# mainboard.net
KiCad netlist of a schematic drawn in EAGLE
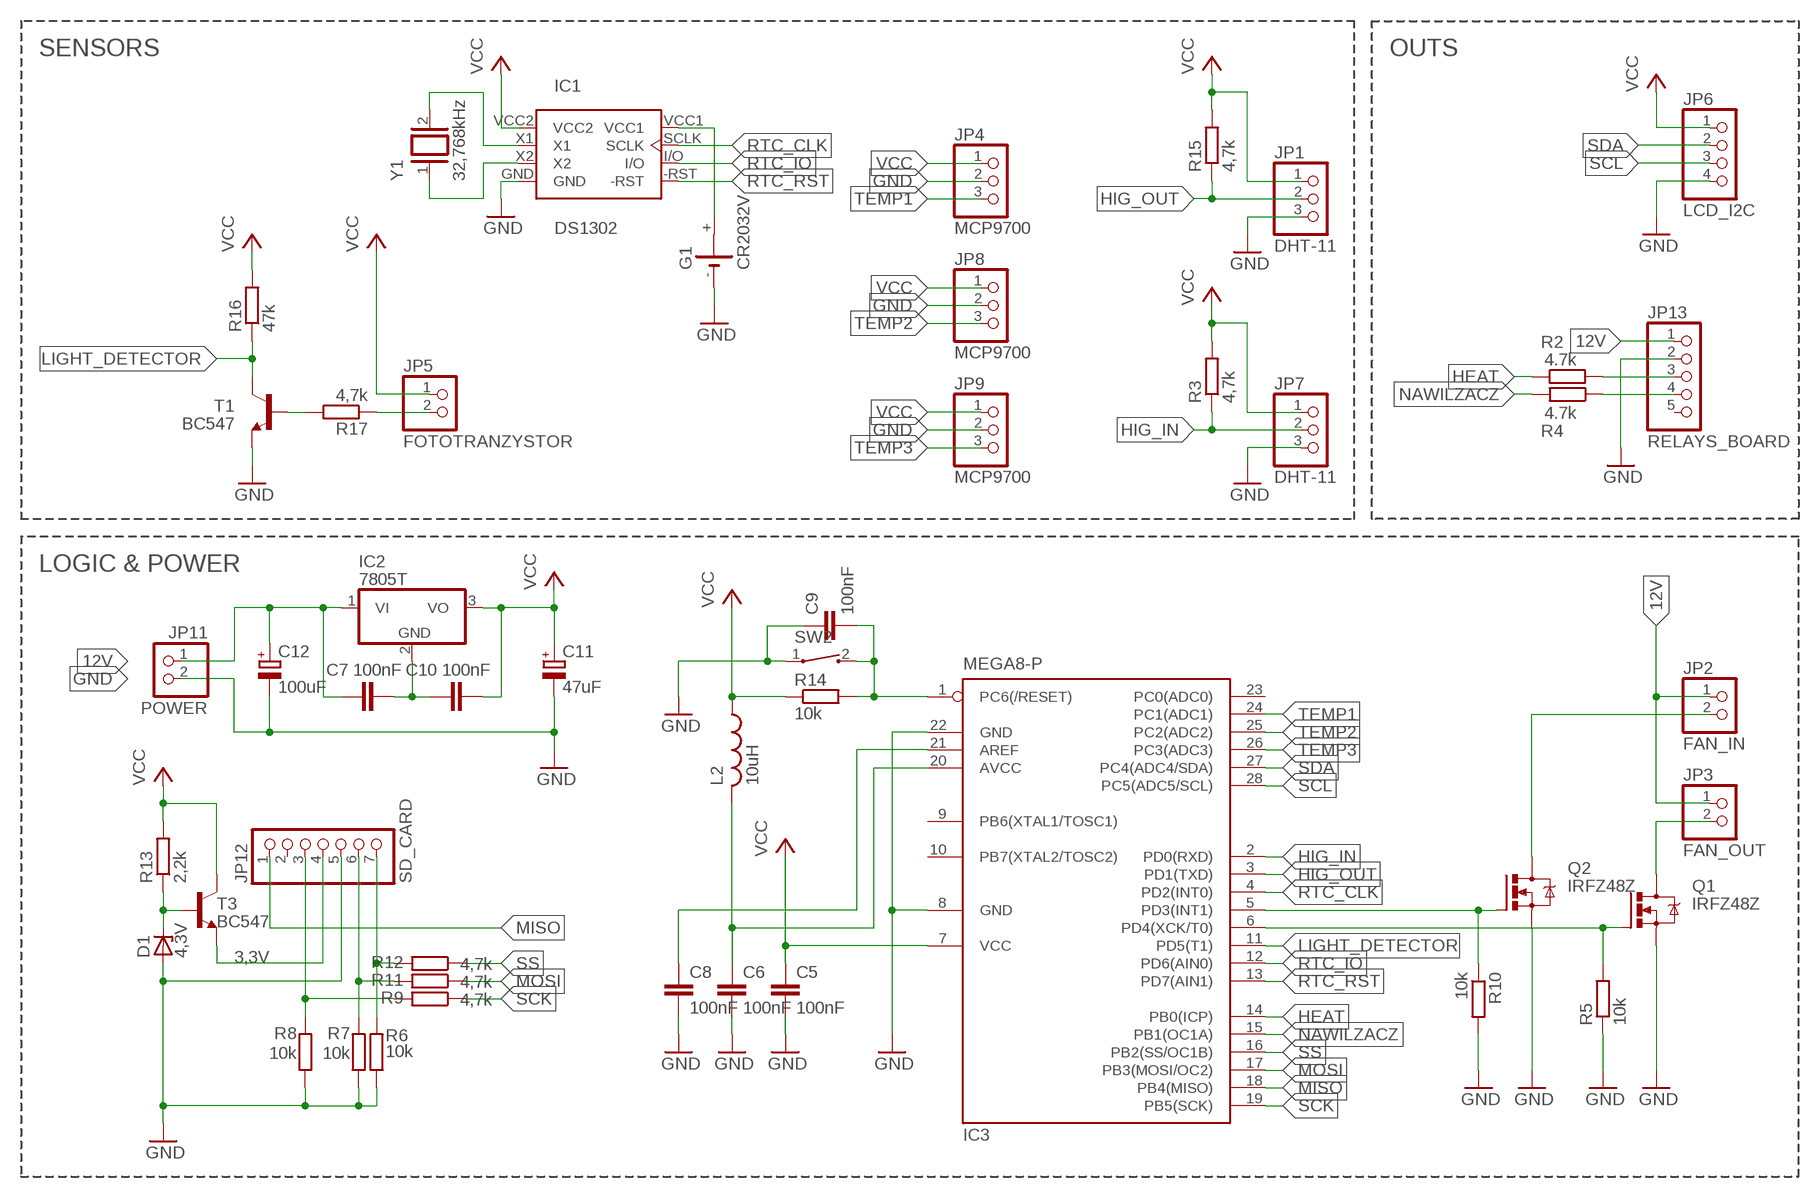
[diagram p0: schematic, sheet 1]

(export (version "E")
  (design (tool "Eeschema 10.0.6"))
  (components
    (comp (ref "C5")
      (value "100nF")
      (footprint "eagle-import:C050-030X075")
      (libsource (lib "eagle-import") (part "C-EU050-030X075"))
    )
    (comp (ref "C6")
      (value "100nF")
      (footprint "eagle-import:C050-030X075")
      (libsource (lib "eagle-import") (part "C-EU050-030X075"))
    )
    (comp (ref "C7")
      (value "100nF")
      (footprint "eagle-import:C050-024X044")
      (libsource (lib "eagle-import") (part "C-EU050-024X044"))
    )
    (comp (ref "C8")
      (value "100nF")
      (footprint "eagle-import:C050-030X075")
      (libsource (lib "eagle-import") (part "C-EU050-030X075"))
    )
    (comp (ref "C9")
      (value "100nF")
      (footprint "eagle-import:C050-030X075")
      (libsource (lib "eagle-import") (part "C-EU050-030X075"))
    )
    (comp (ref "C10")
      (value "100nF")
      (footprint "eagle-import:C050-024X044")
      (libsource (lib "eagle-import") (part "C-EU050-024X044"))
    )
    (comp (ref "C11")
      (value "47uF")
      (footprint "eagle-import:E2,5-6")
      (libsource (lib "eagle-import") (part "CPOL-EUE2.5-6"))
    )
    (comp (ref "C12")
      (value "100uF")
      (footprint "eagle-import:E2,5-6")
      (libsource (lib "eagle-import") (part "CPOL-EUE2.5-6"))
    )
    (comp (ref "D1")
      (value "4,3V")
      (footprint "eagle-import:C1702-15")
      (libsource (lib "eagle-import") (part "ZENER-DIODEC1702-15"))
    )
    (comp (ref "G1")
      (value "CR2032V")
      (footprint "eagle-import:CR2032V")
      (libsource (lib "eagle-import") (part "CR2032V"))
    )
    (comp (ref "IC1")
      (value "DS1302")
      (footprint "eagle-import:DIL08")
      (libsource (lib "eagle-import") (part "DS1302"))
    )
    (comp (ref "IC2")
      (value "7805T")
      (footprint "eagle-import:TO220H")
      (libsource (lib "eagle-import") (part "78T05"))
    )
    (comp (ref "IC3")
      (value "MEGA8-P")
      (footprint "eagle-import:DIL28-3")
      (libsource (lib "eagle-import") (part "MEGA8-P"))
    )
    (comp (ref "JP1")
      (value "DHT-11")
      (footprint "eagle-import:1X03")
      (libsource (lib "eagle-import") (part "PINHD-1X3"))
    )
    (comp (ref "JP2")
      (value "FAN_IN")
      (footprint "eagle-import:1X02")
      (libsource (lib "eagle-import") (part "PINHD-1X2"))
    )
    (comp (ref "JP3")
      (value "FAN_OUT")
      (footprint "eagle-import:1X02")
      (libsource (lib "eagle-import") (part "PINHD-1X2"))
    )
    (comp (ref "JP4")
      (value "MCP9700")
      (footprint "eagle-import:1X03")
      (libsource (lib "eagle-import") (part "PINHD-1X3"))
    )
    (comp (ref "JP5")
      (value "FOTOTRANZYSTOR")
      (footprint "eagle-import:1X02")
      (libsource (lib "eagle-import") (part "PINHD-1X2"))
    )
    (comp (ref "JP6")
      (value "LCD_I2C")
      (footprint "eagle-import:1X04")
      (libsource (lib "eagle-import") (part "PINHD-1X4"))
    )
    (comp (ref "JP7")
      (value "DHT-11")
      (footprint "eagle-import:1X03")
      (libsource (lib "eagle-import") (part "PINHD-1X3"))
    )
    (comp (ref "JP8")
      (value "MCP9700")
      (footprint "eagle-import:1X03")
      (libsource (lib "eagle-import") (part "PINHD-1X3"))
    )
    (comp (ref "JP9")
      (value "MCP9700")
      (footprint "eagle-import:1X03")
      (libsource (lib "eagle-import") (part "PINHD-1X3"))
    )
    (comp (ref "JP11")
      (value "POWER")
      (footprint "eagle-import:1X02")
      (libsource (lib "eagle-import") (part "PINHD-1X2"))
    )
    (comp (ref "JP12")
      (value "SD_CARD")
      (footprint "eagle-import:1X07")
      (libsource (lib "eagle-import") (part "PINHD-1X7"))
    )
    (comp (ref "JP13")
      (value "RELAYS_BOARD")
      (footprint "eagle-import:1X05")
      (libsource (lib "eagle-import") (part "PINHD-1X5"))
    )
    (comp (ref "L2")
      (value "10uH")
      (footprint "eagle-import:0204_7")
      (libsource (lib "eagle-import") (part "L-US0204/7"))
    )
    (comp (ref "Q1")
      (value "IRFZ48Z")
      (footprint "eagle-import:TO220BH")
      (libsource (lib "eagle-import") (part "IRFZ48Z"))
    )
    (comp (ref "Q2")
      (value "IRFZ48Z")
      (footprint "eagle-import:TO220BH")
      (libsource (lib "eagle-import") (part "IRFZ48Z"))
    )
    (comp (ref "R2")
      (value "4.7k")
      (footprint "eagle-import:0207_10")
      (libsource (lib "eagle-import") (part "R-EU_0207/10"))
    )
    (comp (ref "R3")
      (value "4,7k")
      (footprint "eagle-import:0207_10")
      (libsource (lib "eagle-import") (part "R-EU_0207/10"))
    )
    (comp (ref "R4")
      (value "4.7k")
      (footprint "eagle-import:0207_10")
      (libsource (lib "eagle-import") (part "R-EU_0207/10"))
    )
    (comp (ref "R5")
      (value "10k")
      (footprint "eagle-import:0207_10")
      (libsource (lib "eagle-import") (part "R-EU_0207/10"))
    )
    (comp (ref "R6")
      (value "10k")
      (footprint "eagle-import:0207_10")
      (libsource (lib "eagle-import") (part "R-EU_0207/10"))
    )
    (comp (ref "R7")
      (value "10k")
      (footprint "eagle-import:0207_10")
      (libsource (lib "eagle-import") (part "R-EU_0207/10"))
    )
    (comp (ref "R8")
      (value "10k")
      (footprint "eagle-import:0207_10")
      (libsource (lib "eagle-import") (part "R-EU_0207/10"))
    )
    (comp (ref "R9")
      (value "4,7k")
      (footprint "eagle-import:0207_10")
      (libsource (lib "eagle-import") (part "R-EU_0207/10"))
    )
    (comp (ref "R10")
      (value "10k")
      (footprint "eagle-import:0207_10")
      (libsource (lib "eagle-import") (part "R-EU_0207/10"))
    )
    (comp (ref "R11")
      (value "4,7k")
      (footprint "eagle-import:0207_10")
      (libsource (lib "eagle-import") (part "R-EU_0207/10"))
    )
    (comp (ref "R12")
      (value "4,7k")
      (footprint "eagle-import:0207_10")
      (libsource (lib "eagle-import") (part "R-EU_0207/10"))
    )
    (comp (ref "R13")
      (value "2,2k")
      (footprint "eagle-import:0207_10")
      (libsource (lib "eagle-import") (part "R-EU_0207/10"))
    )
    (comp (ref "R14")
      (value "10k")
      (footprint "eagle-import:0204_7")
      (libsource (lib "eagle-import") (part "R-EU_0204/7"))
    )
    (comp (ref "R15")
      (value "4,7k")
      (footprint "eagle-import:0207_10")
      (libsource (lib "eagle-import") (part "R-EU_0207/10"))
    )
    (comp (ref "R16")
      (value "47k")
      (footprint "eagle-import:0207_10")
      (libsource (lib "eagle-import") (part "R-EU_0207/10"))
    )
    (comp (ref "R17")
      (value "4,7k")
      (footprint "eagle-import:0207_10")
      (libsource (lib "eagle-import") (part "R-EU_0207/10"))
    )
    (comp (ref "SW2")
      (value "CT10-XXXX-G4")
      (footprint "eagle-import:CT10-XXXX-G4")
      (libsource (lib "eagle-import") (part "CT10-XXXX-G4"))
    )
    (comp (ref "T1")
      (value "BC547")
      (footprint "eagle-import:TO92")
      (libsource (lib "eagle-import") (part "BC547"))
    )
    (comp (ref "T3")
      (value "BC547")
      (footprint "eagle-import:TO92")
      (libsource (lib "eagle-import") (part "BC547"))
    )
    (comp (ref "Y1")
      (value "32,768kHz")
      (footprint "eagle-import:QS")
      (libsource (lib "eagle-import") (part "XTAL/S"))
    )
  )
  (nets
    (net (code "1") (name "/3,3V") (class "Default")
      (node (ref "JP12") (pin "4") (pinfunction "4_4") (pintype "passive"))
      (node (ref "T3") (pin "1") (pinfunction "E_1") (pintype "passive"))
    )
    (net (code "2") (name "12V") (class "Default")
      (node (ref "C12") (pin "+") (pinfunction "+_+") (pintype "passive"))
      (node (ref "C7") (pin "1") (pinfunction "1_1") (pintype "passive"))
      (node (ref "IC2") (pin "1") (pinfunction "VI_1") (pintype "input"))
      (node (ref "JP11") (pin "1") (pinfunction "1_1") (pintype "passive"))
      (node (ref "JP13") (pin "1") (pinfunction "1_1") (pintype "passive"))
      (node (ref "JP2") (pin "1") (pinfunction "1_1") (pintype "passive"))
      (node (ref "JP3") (pin "1") (pinfunction "1_1") (pintype "passive"))
    )
    (net (code "3") (name "GND") (class "Default")
      (node (ref "C11") (pin "-") (pinfunction "-_-") (pintype "passive"))
      (node (ref "C12") (pin "-") (pinfunction "-_-") (pintype "passive"))
      (node (ref "C5") (pin "2") (pinfunction "2_2") (pintype "passive"))
      (node (ref "C6") (pin "2") (pinfunction "2_2") (pintype "passive"))
      (node (ref "C8") (pin "2") (pinfunction "2_2") (pintype "passive"))
      (node (ref "C9") (pin "1") (pinfunction "1_1") (pintype "passive"))
      (node (ref "D1") (pin "A") (pinfunction "A_A") (pintype "passive"))
      (node (ref "G1") (pin "-") (pinfunction "-_-") (pintype "passive"))
      (node (ref "IC1") (pin "GND") (pinfunction "GND_GND") (pintype "passive"))
      (node (ref "IC3") (pin "22") (pinfunction "GND_22") (pintype "power_in"))
      (node (ref "IC3") (pin "8") (pinfunction "GND_8") (pintype "power_in"))
      (node (ref "JP1") (pin "3") (pinfunction "3_3") (pintype "passive"))
      (node (ref "JP11") (pin "2") (pinfunction "2_2") (pintype "passive"))
      (node (ref "JP12") (pin "5") (pinfunction "5_5") (pintype "passive"))
      (node (ref "JP13") (pin "2") (pinfunction "2_2") (pintype "passive"))
      (node (ref "JP4") (pin "2") (pinfunction "2_2") (pintype "passive"))
      (node (ref "JP6") (pin "4") (pinfunction "4_4") (pintype "passive"))
      (node (ref "JP7") (pin "3") (pinfunction "3_3") (pintype "passive"))
      (node (ref "JP8") (pin "2") (pinfunction "2_2") (pintype "passive"))
      (node (ref "JP9") (pin "2") (pinfunction "2_2") (pintype "passive"))
      (node (ref "Q1") (pin "S") (pinfunction "S_S") (pintype "passive"))
      (node (ref "Q2") (pin "S") (pinfunction "S_S") (pintype "passive"))
      (node (ref "R10") (pin "2") (pinfunction "2_2") (pintype "passive"))
      (node (ref "R5") (pin "1") (pinfunction "1_1") (pintype "passive"))
      (node (ref "R6") (pin "1") (pinfunction "1_1") (pintype "passive"))
      (node (ref "R7") (pin "1") (pinfunction "1_1") (pintype "passive"))
      (node (ref "R8") (pin "1") (pinfunction "1_1") (pintype "passive"))
      (node (ref "SW2") (pin "1") (pinfunction "1_1") (pintype "passive"))
      (node (ref "T1") (pin "1") (pinfunction "E_1") (pintype "passive"))
    )
    (net (code "4") (name "HEAT") (class "Default")
      (node (ref "IC3") (pin "14") (pinfunction "PB0(ICP)_14") (pintype "bidirectional"))
      (node (ref "R2") (pin "1") (pinfunction "1_1") (pintype "passive"))
    )
    (net (code "5") (name "HIG_IN") (class "Default")
      (node (ref "IC3") (pin "2") (pinfunction "PD0(RXD)_2") (pintype "bidirectional"))
      (node (ref "JP7") (pin "2") (pinfunction "2_2") (pintype "passive"))
      (node (ref "R3") (pin "1") (pinfunction "1_1") (pintype "passive"))
    )
    (net (code "6") (name "HIG_OUT") (class "Default")
      (node (ref "IC3") (pin "3") (pinfunction "PD1(TXD)_3") (pintype "bidirectional"))
      (node (ref "JP1") (pin "2") (pinfunction "2_2") (pintype "passive"))
      (node (ref "R15") (pin "1") (pinfunction "1_1") (pintype "passive"))
    )
    (net (code "7") (name "LIGHT_DETECTOR") (class "Default")
      (node (ref "IC3") (pin "11") (pinfunction "PD5(T1)_11") (pintype "bidirectional"))
      (node (ref "IC3") (pin "6") (pinfunction "PD4(XCK/T0)_6") (pintype "bidirectional"))
      (node (ref "Q1") (pin "G") (pinfunction "G_G") (pintype "passive"))
      (node (ref "R16") (pin "1") (pinfunction "1_1") (pintype "passive"))
      (node (ref "R5") (pin "2") (pinfunction "2_2") (pintype "passive"))
      (node (ref "T1") (pin "3") (pinfunction "C_3") (pintype "passive"))
    )
    (net (code "8") (name "MISO") (class "Default")
      (node (ref "IC3") (pin "18") (pinfunction "PB4(MISO)_18") (pintype "bidirectional"))
      (node (ref "JP12") (pin "1") (pinfunction "1_1") (pintype "passive"))
    )
    (net (code "9") (name "MOSI") (class "Default")
      (node (ref "IC3") (pin "17") (pinfunction "PB3(MOSI/OC2)_17") (pintype "bidirectional"))
      (node (ref "R11") (pin "1") (pinfunction "1_1") (pintype "passive"))
    )
    (net (code "10") (name "NAWILZACZ") (class "Default")
      (node (ref "IC3") (pin "15") (pinfunction "PB1(OC1A)_15") (pintype "bidirectional"))
      (node (ref "R4") (pin "2") (pinfunction "2_2") (pintype "passive"))
    )
    (net (code "11") (name "Net-(G1-Pad+)") (class "Default")
      (node (ref "G1") (pin "+") (pinfunction "+_+") (pintype "passive"))
      (node (ref "IC1") (pin "VCC1") (pinfunction "VCC1_VCC1") (pintype "power_in"))
    )
    (net (code "12") (name "Net-(IC1-PadX1)") (class "Default")
      (node (ref "IC1") (pin "X1") (pinfunction "X1_X1") (pintype "tri_state"))
      (node (ref "Y1") (pin "2") (pinfunction "2_2") (pintype "passive"))
    )
    (net (code "13") (name "Net-(IC1-PadX2)") (class "Default")
      (node (ref "IC1") (pin "X2") (pinfunction "X2_X2") (pintype "tri_state"))
      (node (ref "Y1") (pin "1") (pinfunction "1_1") (pintype "passive"))
    )
    (net (code "14") (name "Net-(IC2-GND)") (class "Default")
      (node (ref "C10") (pin "1") (pinfunction "1_1") (pintype "passive"))
      (node (ref "C7") (pin "2") (pinfunction "2_2") (pintype "passive"))
      (node (ref "IC2") (pin "2") (pinfunction "GND_2") (pintype "passive"))
    )
    (net (code "15") (name "Net-(IC3-AREF)") (class "Default")
      (node (ref "C8") (pin "1") (pinfunction "1_1") (pintype "passive"))
      (node (ref "IC3") (pin "21") (pinfunction "AREF_21") (pintype "passive"))
    )
    (net (code "16") (name "Net-(IC3-AVCC)") (class "Default")
      (node (ref "C6") (pin "1") (pinfunction "1_1") (pintype "passive"))
      (node (ref "IC3") (pin "20") (pinfunction "AVCC_20") (pintype "power_in"))
      (node (ref "L2") (pin "2") (pinfunction "2_2") (pintype "passive"))
    )
    (net (code "17") (name "Net-(IC3-PC6({slash}RESET))") (class "Default")
      (node (ref "C9") (pin "2") (pinfunction "2_2") (pintype "passive"))
      (node (ref "IC3") (pin "1") (pinfunction "PC6(/RESET)_1") (pintype "bidirectional"))
      (node (ref "R14") (pin "2") (pinfunction "2_2") (pintype "passive"))
      (node (ref "SW2") (pin "2") (pinfunction "2_2") (pintype "passive"))
    )
    (net (code "18") (name "Net-(IC3-PD3(INT1))") (class "Default")
      (node (ref "IC3") (pin "5") (pinfunction "PD3(INT1)_5") (pintype "bidirectional"))
      (node (ref "Q2") (pin "G") (pinfunction "G_G") (pintype "passive"))
      (node (ref "R10") (pin "1") (pinfunction "1_1") (pintype "passive"))
    )
    (net (code "19") (name "Net-(JP2-Pad2)") (class "Default")
      (node (ref "JP2") (pin "2") (pinfunction "2_2") (pintype "passive"))
      (node (ref "Q2") (pin "D") (pinfunction "D_D") (pintype "passive"))
    )
    (net (code "20") (name "Net-(JP3-Pad2)") (class "Default")
      (node (ref "JP3") (pin "2") (pinfunction "2_2") (pintype "passive"))
      (node (ref "Q1") (pin "D") (pinfunction "D_D") (pintype "passive"))
    )
    (net (code "21") (name "Net-(JP5-Pad2)") (class "Default")
      (node (ref "JP5") (pin "2") (pinfunction "2_2") (pintype "passive"))
      (node (ref "R17") (pin "1") (pinfunction "1_1") (pintype "passive"))
    )
    (net (code "22") (name "Net-(JP12-Pad3)") (class "Default")
      (node (ref "JP12") (pin "3") (pinfunction "3_3") (pintype "passive"))
      (node (ref "R8") (pin "2") (pinfunction "2_2") (pintype "passive"))
      (node (ref "R9") (pin "2") (pinfunction "2_2") (pintype "passive"))
    )
    (net (code "23") (name "Net-(JP12-Pad6)") (class "Default")
      (node (ref "JP12") (pin "6") (pinfunction "6_6") (pintype "passive"))
      (node (ref "R11") (pin "2") (pinfunction "2_2") (pintype "passive"))
      (node (ref "R7") (pin "2") (pinfunction "2_2") (pintype "passive"))
    )
    (net (code "24") (name "Net-(JP12-Pad7)") (class "Default")
      (node (ref "JP12") (pin "7") (pinfunction "7_7") (pintype "passive"))
      (node (ref "R12") (pin "2") (pinfunction "2_2") (pintype "passive"))
      (node (ref "R6") (pin "2") (pinfunction "2_2") (pintype "passive"))
    )
    (net (code "25") (name "Net-(JP13-Pad3)") (class "Default")
      (node (ref "JP13") (pin "3") (pinfunction "3_3") (pintype "passive"))
      (node (ref "R2") (pin "2") (pinfunction "2_2") (pintype "passive"))
    )
    (net (code "26") (name "Net-(JP13-Pad4)") (class "Default")
      (node (ref "JP13") (pin "4") (pinfunction "4_4") (pintype "passive"))
      (node (ref "R4") (pin "1") (pinfunction "1_1") (pintype "passive"))
    )
    (net (code "27") (name "Net-(T1-B)") (class "Default")
      (node (ref "R17") (pin "2") (pinfunction "2_2") (pintype "passive"))
      (node (ref "T1") (pin "2") (pinfunction "B_2") (pintype "passive"))
    )
    (net (code "28") (name "Net-(T3-B)") (class "Default")
      (node (ref "D1") (pin "C") (pinfunction "C_C") (pintype "passive"))
      (node (ref "R13") (pin "1") (pinfunction "1_1") (pintype "passive"))
      (node (ref "T3") (pin "2") (pinfunction "B_2") (pintype "passive"))
    )
    (net (code "29") (name "RTC_CLK") (class "Default")
      (node (ref "IC1") (pin "SCLK") (pinfunction "SCLK_SCLK") (pintype "tri_state"))
      (node (ref "IC3") (pin "4") (pinfunction "PD2(INT0)_4") (pintype "bidirectional"))
    )
    (net (code "30") (name "RTC_IO") (class "Default")
      (node (ref "IC1") (pin "I/O") (pinfunction "I/O_I/O") (pintype "bidirectional"))
      (node (ref "IC3") (pin "12") (pinfunction "PD6(AIN0)_12") (pintype "bidirectional"))
    )
    (net (code "31") (name "RTC_RST") (class "Default")
      (node (ref "IC1") (pin "-RST") (pinfunction "-RST_-RST") (pintype "bidirectional"))
      (node (ref "IC3") (pin "13") (pinfunction "PD7(AIN1)_13") (pintype "bidirectional"))
    )
    (net (code "32") (name "SCK") (class "Default")
      (node (ref "IC3") (pin "19") (pinfunction "PB5(SCK)_19") (pintype "bidirectional"))
      (node (ref "R9") (pin "1") (pinfunction "1_1") (pintype "passive"))
    )
    (net (code "33") (name "SCL") (class "Default")
      (node (ref "IC3") (pin "28") (pinfunction "PC5(ADC5/SCL)_28") (pintype "bidirectional"))
      (node (ref "JP6") (pin "3") (pinfunction "3_3") (pintype "passive"))
    )
    (net (code "34") (name "SDA") (class "Default")
      (node (ref "IC3") (pin "27") (pinfunction "PC4(ADC4/SDA)_27") (pintype "bidirectional"))
      (node (ref "JP6") (pin "2") (pinfunction "2_2") (pintype "passive"))
    )
    (net (code "35") (name "SS") (class "Default")
      (node (ref "IC3") (pin "16") (pinfunction "PB2(SS/OC1B)_16") (pintype "bidirectional"))
      (node (ref "R12") (pin "1") (pinfunction "1_1") (pintype "passive"))
    )
    (net (code "36") (name "TEMP1") (class "Default")
      (node (ref "IC3") (pin "24") (pinfunction "PC1(ADC1)_24") (pintype "bidirectional"))
      (node (ref "JP4") (pin "3") (pinfunction "3_3") (pintype "passive"))
    )
    (net (code "37") (name "TEMP2") (class "Default")
      (node (ref "IC3") (pin "25") (pinfunction "PC2(ADC2)_25") (pintype "bidirectional"))
      (node (ref "JP8") (pin "3") (pinfunction "3_3") (pintype "passive"))
    )
    (net (code "38") (name "TEMP3") (class "Default")
      (node (ref "IC3") (pin "26") (pinfunction "PC3(ADC3)_26") (pintype "bidirectional"))
      (node (ref "JP9") (pin "3") (pinfunction "3_3") (pintype "passive"))
    )
    (net (code "39") (name "VCC") (class "Default")
      (node (ref "C10") (pin "2") (pinfunction "2_2") (pintype "passive"))
      (node (ref "C11") (pin "+") (pinfunction "+_+") (pintype "passive"))
      (node (ref "C5") (pin "1") (pinfunction "1_1") (pintype "passive"))
      (node (ref "IC1") (pin "VCC2") (pinfunction "VCC2_VCC2") (pintype "power_in"))
      (node (ref "IC2") (pin "3") (pinfunction "VO_3") (pintype "passive"))
      (node (ref "IC3") (pin "7") (pinfunction "VCC_7") (pintype "power_in"))
      (node (ref "JP1") (pin "1") (pinfunction "1_1") (pintype "passive"))
      (node (ref "JP4") (pin "1") (pinfunction "1_1") (pintype "passive"))
      (node (ref "JP5") (pin "1") (pinfunction "1_1") (pintype "passive"))
      (node (ref "JP6") (pin "1") (pinfunction "1_1") (pintype "passive"))
      (node (ref "JP7") (pin "1") (pinfunction "1_1") (pintype "passive"))
      (node (ref "JP8") (pin "1") (pinfunction "1_1") (pintype "passive"))
      (node (ref "JP9") (pin "1") (pinfunction "1_1") (pintype "passive"))
      (node (ref "L2") (pin "1") (pinfunction "1_1") (pintype "passive"))
      (node (ref "R13") (pin "2") (pinfunction "2_2") (pintype "passive"))
      (node (ref "R14") (pin "1") (pinfunction "1_1") (pintype "passive"))
      (node (ref "R15") (pin "2") (pinfunction "2_2") (pintype "passive"))
      (node (ref "R16") (pin "2") (pinfunction "2_2") (pintype "passive"))
      (node (ref "R3") (pin "2") (pinfunction "2_2") (pintype "passive"))
      (node (ref "T3") (pin "3") (pinfunction "C_3") (pintype "passive"))
    )
    (net (code "40") (name "unconnected-(G1-+-Pad+@1)") (class "Default")
      (node (ref "G1") (pin "+@1") (pinfunction "+_+@1") (pintype "passive"))
    )
    (net (code "41") (name "unconnected-(IC3-PB6(XTAL1{slash}TOSC1)-Pad9)") (class "Default")
      (node (ref "IC3") (pin "9") (pinfunction "PB6(XTAL1/TOSC1)_9") (pintype "bidirectional"))
    )
    (net (code "42") (name "unconnected-(IC3-PB7(XTAL2{slash}TOSC2)-Pad10)") (class "Default")
      (node (ref "IC3") (pin "10") (pinfunction "PB7(XTAL2/TOSC2)_10") (pintype "bidirectional"))
    )
    (net (code "43") (name "unconnected-(IC3-PC0(ADC0)-Pad23)") (class "Default")
      (node (ref "IC3") (pin "23") (pinfunction "PC0(ADC0)_23") (pintype "bidirectional"))
    )
    (net (code "44") (name "unconnected-(JP12-Pad2)") (class "Default")
      (node (ref "JP12") (pin "2") (pinfunction "2_2") (pintype "passive"))
    )
    (net (code "45") (name "unconnected-(JP13-Pad5)") (class "Default")
      (node (ref "JP13") (pin "5") (pinfunction "5_5") (pintype "passive"))
    )
  )
)
